# Cama_caliente.net
KiCad netlist of a schematic drawn in Altium Designer
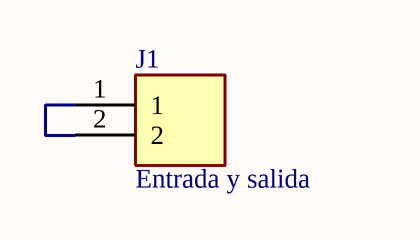
[diagram p0: Cama caliente.SchDoc]

(export (version "E")
  (design (tool "Eeschema 10.0.6"))
  (components
    (comp (ref "J1")
      (value "282841-2")
      (footprint "TE_282841-2")
      (description "Conn Terminal Block 2 POS 5.08mm Solder ST Thru-Hole 17.5A/Contact")
      (fields (field (name "MF") "TE Connectivity") (field (name "COMMENT_1") "Entrada y salida"))
      (libsource (lib "282841-2") (part "282841-2"))
    )
  )
  (nets
    (net (code "1") (name "Net-(J1-Pad1)") (class "Default")
      (node (ref "J1") (pin "1") (pinfunction "1_1") (pintype "passive"))
      (node (ref "J1") (pin "2") (pinfunction "2_2") (pintype "passive"))
    )
  )
)
